# power.net
KiCad netlist of a schematic drawn in EAGLE
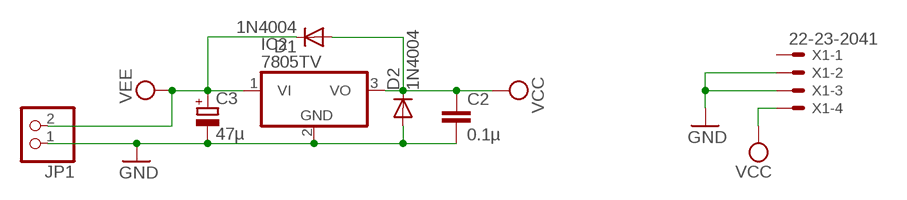
[diagram p0: schematic, sheet 1]

(export (version "E")
  (design (tool "Eeschema 10.0.6"))
  (components
    (comp (ref "C2")
      (value "0.1µ")
      (footprint "eagle-import:C025-024X044")
      (libsource (lib "eagle-import") (part "C-EU025-024X044"))
    )
    (comp (ref "C3")
      (value "47µ")
      (footprint "eagle-import:E5-4")
      (libsource (lib "eagle-import") (part "CPOL-EUE5-4"))
    )
    (comp (ref "D1")
      (value "1N4004")
      (footprint "eagle-import:DO41-10")
      (libsource (lib "eagle-import") (part "1N4004"))
    )
    (comp (ref "D2")
      (value "1N4004")
      (footprint "eagle-import:DO41-10")
      (libsource (lib "eagle-import") (part "1N4004"))
    )
    (comp (ref "IC2")
      (value "7805TV")
      (footprint "eagle-import:TO220V")
      (libsource (lib "eagle-import") (part "78TV05"))
    )
    (comp (ref "JP1")
      (value "PINHD-1X2")
      (footprint "eagle-import:1X02")
      (libsource (lib "eagle-import") (part "PINHD-1X2"))
    )
    (comp (ref "X1")
      (value "22-23-2041")
      (footprint "eagle-import:22-23-2041")
      (fields (field (name "MF") "MOLEX"))
      (libsource (lib "eagle-import") (part "22-23-2041"))
    )
  )
  (nets
    (net (code "1") (name "GND") (class "Default")
      (node (ref "C2") (pin "2") (pinfunction "2_2") (pintype "passive"))
      (node (ref "C3") (pin "-") (pinfunction "-_-") (pintype "passive"))
      (node (ref "D2") (pin "A") (pinfunction "A_A") (pintype "passive"))
      (node (ref "IC2") (pin "2") (pinfunction "GND_2") (pintype "passive"))
      (node (ref "JP1") (pin "1") (pinfunction "1_1") (pintype "passive"))
      (node (ref "X1") (pin "2") (pinfunction "S_2") (pintype "passive"))
      (node (ref "X1") (pin "3") (pinfunction "S_3") (pintype "passive"))
    )
    (net (code "2") (name "VCC") (class "Default")
      (node (ref "C2") (pin "1") (pinfunction "1_1") (pintype "passive"))
      (node (ref "D1") (pin "A") (pinfunction "A_A") (pintype "passive"))
      (node (ref "D2") (pin "C") (pinfunction "C_C") (pintype "passive"))
      (node (ref "IC2") (pin "3") (pinfunction "VO_3") (pintype "passive"))
      (node (ref "X1") (pin "4") (pinfunction "S_4") (pintype "passive"))
    )
    (net (code "3") (name "VEE") (class "Default")
      (node (ref "C3") (pin "+") (pinfunction "+_+") (pintype "passive"))
      (node (ref "D1") (pin "C") (pinfunction "C_C") (pintype "passive"))
      (node (ref "IC2") (pin "1") (pinfunction "VI_1") (pintype "input"))
      (node (ref "JP1") (pin "2") (pinfunction "2_2") (pintype "passive"))
    )
    (net (code "4") (name "unconnected-(X1A-S-Pad1)") (class "Default")
      (node (ref "X1") (pin "1") (pinfunction "S_1") (pintype "passive"))
    )
  )
)
